# DDR4_Conn.net
KiCad netlist of a schematic drawn in Altium Designer
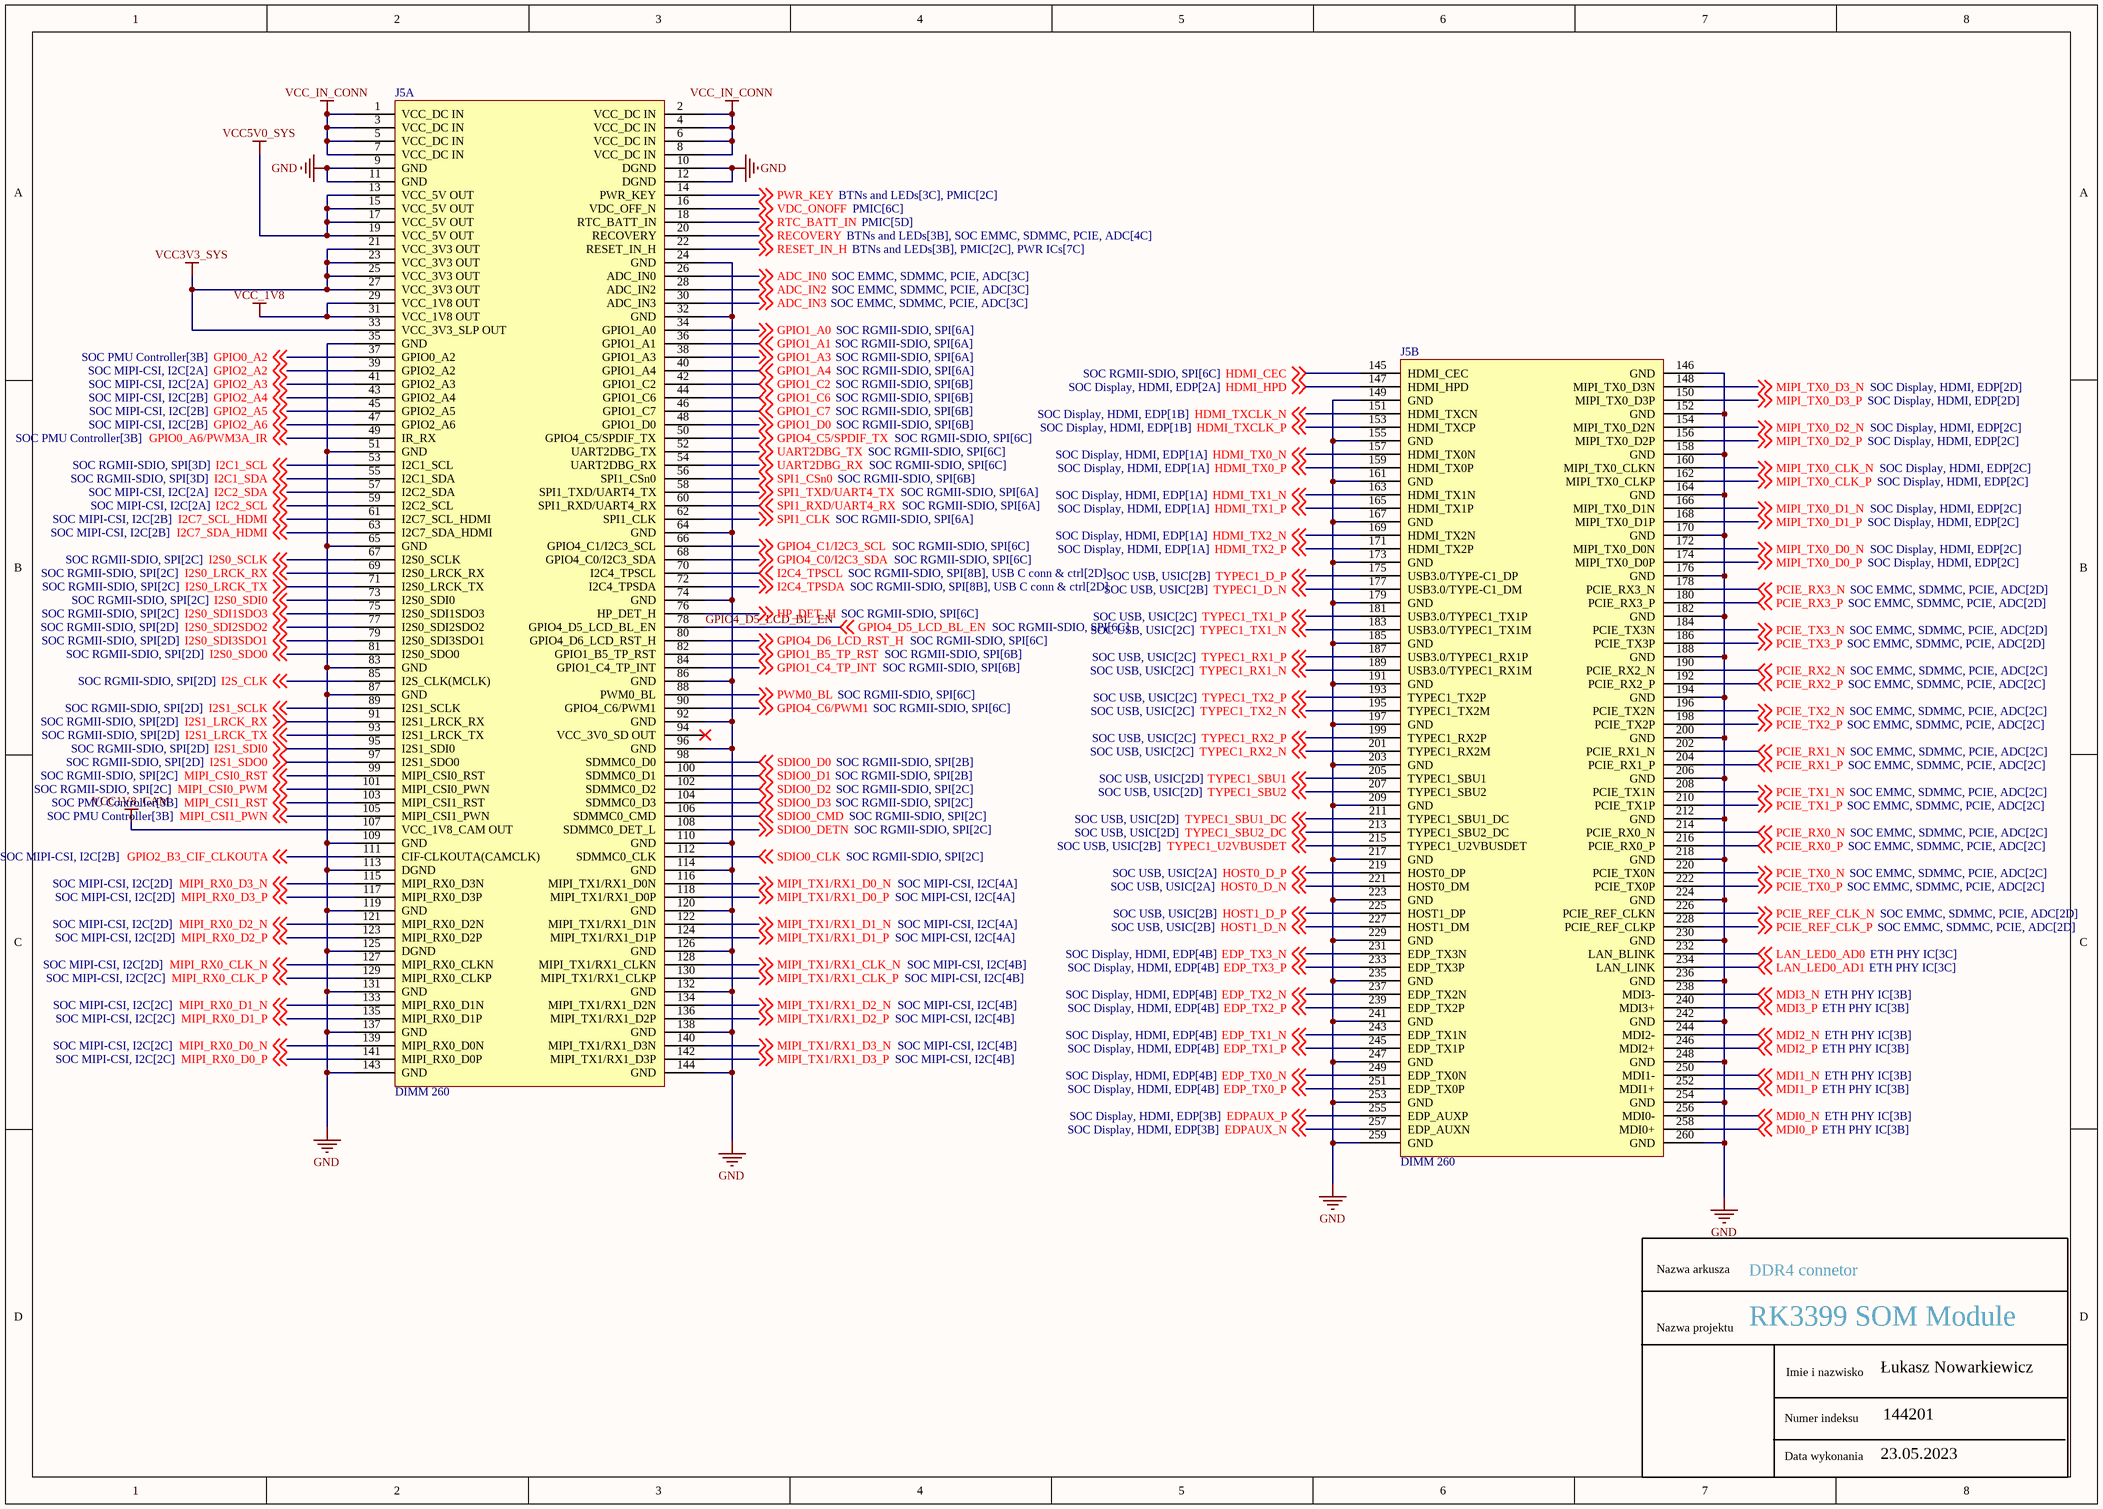
[diagram p0: DDR4 Conn.SchDoc]

(export (version "E")
  (design (tool "Eeschema 10.0.6"))
  (components
    (comp (ref "J5")
      (value "DIMM 260")
      (footprint "DIMM260_DDR4")
      (description "Dimm 260 pin smd plating on pcb")
      (fields (field (name "MANUFACTURER") "NA"))
      (libsource (lib "RK3399 _Module_Schlib") (part "CON-DIMM_260-SMD"))
    )
  )
  (nets
    (net (code "1") (name "ADC_IN0") (class "Default")
      (node (ref "J5") (pin "26") (pinfunction "ADC_IN0_26") (pintype "passive"))
    )
    (net (code "2") (name "ADC_IN2") (class "Default")
      (node (ref "J5") (pin "28") (pinfunction "ADC_IN2_28") (pintype "passive"))
    )
    (net (code "3") (name "ADC_IN3") (class "Default")
      (node (ref "J5") (pin "30") (pinfunction "ADC_IN3_30") (pintype "passive"))
    )
    (net (code "4") (name "EDPAUX_N") (class "Default")
      (node (ref "J5") (pin "257") (pinfunction "EDP_AUXN_257") (pintype "passive"))
    )
    (net (code "5") (name "EDPAUX_P") (class "Default")
      (node (ref "J5") (pin "255") (pinfunction "EDP_AUXP_255") (pintype "passive"))
    )
    (net (code "6") (name "EDP_TX0_N") (class "Default")
      (node (ref "J5") (pin "249") (pinfunction "EDP_TX0N_249") (pintype "passive"))
    )
    (net (code "7") (name "EDP_TX0_P") (class "Default")
      (node (ref "J5") (pin "251") (pinfunction "EDP_TX0P_251") (pintype "passive"))
    )
    (net (code "8") (name "EDP_TX1_N") (class "Default")
      (node (ref "J5") (pin "243") (pinfunction "EDP_TX1N_243") (pintype "passive"))
    )
    (net (code "9") (name "EDP_TX1_P") (class "Default")
      (node (ref "J5") (pin "245") (pinfunction "EDP_TX1P_245") (pintype "passive"))
    )
    (net (code "10") (name "EDP_TX2_N") (class "Default")
      (node (ref "J5") (pin "237") (pinfunction "EDP_TX2N_237") (pintype "passive"))
    )
    (net (code "11") (name "EDP_TX2_P") (class "Default")
      (node (ref "J5") (pin "239") (pinfunction "EDP_TX2P_239") (pintype "passive"))
    )
    (net (code "12") (name "EDP_TX3_N") (class "Default")
      (node (ref "J5") (pin "231") (pinfunction "EDP_TX3N_231") (pintype "passive"))
    )
    (net (code "13") (name "EDP_TX3_P") (class "Default")
      (node (ref "J5") (pin "233") (pinfunction "EDP_TX3P_233") (pintype "passive"))
    )
    (net (code "14") (name "GND") (class "Default")
      (node (ref "J5") (pin "10") (pinfunction "DGND_10") (pintype "passive"))
      (node (ref "J5") (pin "109") (pinfunction "GND_109") (pintype "passive"))
      (node (ref "J5") (pin "11") (pinfunction "GND_11") (pintype "passive"))
      (node (ref "J5") (pin "110") (pinfunction "GND_110") (pintype "passive"))
      (node (ref "J5") (pin "113") (pinfunction "DGND_113") (pintype "passive"))
      (node (ref "J5") (pin "114") (pinfunction "GND_114") (pintype "passive"))
      (node (ref "J5") (pin "119") (pinfunction "GND_119") (pintype "passive"))
      (node (ref "J5") (pin "12") (pinfunction "DGND_12") (pintype "passive"))
      (node (ref "J5") (pin "120") (pinfunction "GND_120") (pintype "passive"))
      (node (ref "J5") (pin "125") (pinfunction "DGND_125") (pintype "passive"))
      (node (ref "J5") (pin "126") (pinfunction "GND_126") (pintype "passive"))
      (node (ref "J5") (pin "131") (pinfunction "GND_131") (pintype "passive"))
      (node (ref "J5") (pin "132") (pinfunction "GND_132") (pintype "passive"))
      (node (ref "J5") (pin "137") (pinfunction "GND_137") (pintype "passive"))
      (node (ref "J5") (pin "138") (pinfunction "GND_138") (pintype "passive"))
      (node (ref "J5") (pin "143") (pinfunction "GND_143") (pintype "passive"))
      (node (ref "J5") (pin "144") (pinfunction "GND_144") (pintype "passive"))
      (node (ref "J5") (pin "146") (pinfunction "GND_146") (pintype "passive"))
      (node (ref "J5") (pin "149") (pinfunction "GND_149") (pintype "passive"))
      (node (ref "J5") (pin "152") (pinfunction "GND_152") (pintype "passive"))
      (node (ref "J5") (pin "155") (pinfunction "GND_155") (pintype "passive"))
      (node (ref "J5") (pin "158") (pinfunction "GND_158") (pintype "passive"))
      (node (ref "J5") (pin "161") (pinfunction "GND_161") (pintype "passive"))
      (node (ref "J5") (pin "164") (pinfunction "GND_164") (pintype "passive"))
      (node (ref "J5") (pin "167") (pinfunction "GND_167") (pintype "passive"))
      (node (ref "J5") (pin "170") (pinfunction "GND_170") (pintype "passive"))
      (node (ref "J5") (pin "173") (pinfunction "GND_173") (pintype "passive"))
      (node (ref "J5") (pin "176") (pinfunction "GND_176") (pintype "passive"))
      (node (ref "J5") (pin "179") (pinfunction "GND_179") (pintype "passive"))
      (node (ref "J5") (pin "182") (pinfunction "GND_182") (pintype "passive"))
      (node (ref "J5") (pin "185") (pinfunction "GND_185") (pintype "passive"))
      (node (ref "J5") (pin "188") (pinfunction "GND_188") (pintype "passive"))
      (node (ref "J5") (pin "191") (pinfunction "GND_191") (pintype "passive"))
      (node (ref "J5") (pin "194") (pinfunction "GND_194") (pintype "passive"))
      (node (ref "J5") (pin "197") (pinfunction "GND_197") (pintype "passive"))
      (node (ref "J5") (pin "200") (pinfunction "GND_200") (pintype "passive"))
      (node (ref "J5") (pin "203") (pinfunction "GND_203") (pintype "passive"))
      (node (ref "J5") (pin "206") (pinfunction "GND_206") (pintype "passive"))
      (node (ref "J5") (pin "209") (pinfunction "GND_209") (pintype "passive"))
      (node (ref "J5") (pin "212") (pinfunction "GND_212") (pintype "passive"))
      (node (ref "J5") (pin "217") (pinfunction "GND_217") (pintype "passive"))
      (node (ref "J5") (pin "218") (pinfunction "GND_218") (pintype "passive"))
      (node (ref "J5") (pin "223") (pinfunction "GND_223") (pintype "passive"))
      (node (ref "J5") (pin "224") (pinfunction "GND_224") (pintype "passive"))
      (node (ref "J5") (pin "229") (pinfunction "GND_229") (pintype "passive"))
      (node (ref "J5") (pin "230") (pinfunction "GND_230") (pintype "passive"))
      (node (ref "J5") (pin "235") (pinfunction "GND_235") (pintype "passive"))
      (node (ref "J5") (pin "236") (pinfunction "GND_236") (pintype "passive"))
      (node (ref "J5") (pin "24") (pinfunction "GND_24") (pintype "passive"))
      (node (ref "J5") (pin "241") (pinfunction "GND_241") (pintype "passive"))
      (node (ref "J5") (pin "242") (pinfunction "GND_242") (pintype "passive"))
      (node (ref "J5") (pin "247") (pinfunction "GND_247") (pintype "passive"))
      (node (ref "J5") (pin "248") (pinfunction "GND_248") (pintype "passive"))
      (node (ref "J5") (pin "253") (pinfunction "GND_253") (pintype "passive"))
      (node (ref "J5") (pin "254") (pinfunction "GND_254") (pintype "passive"))
      (node (ref "J5") (pin "259") (pinfunction "GND_259") (pintype "passive"))
      (node (ref "J5") (pin "260") (pinfunction "GND_260") (pintype "passive"))
      (node (ref "J5") (pin "32") (pinfunction "GND_32") (pintype "passive"))
      (node (ref "J5") (pin "35") (pinfunction "GND_35") (pintype "passive"))
      (node (ref "J5") (pin "51") (pinfunction "GND_51") (pintype "passive"))
      (node (ref "J5") (pin "64") (pinfunction "GND_64") (pintype "passive"))
      (node (ref "J5") (pin "65") (pinfunction "GND_65") (pintype "passive"))
      (node (ref "J5") (pin "74") (pinfunction "GND_74") (pintype "passive"))
      (node (ref "J5") (pin "83") (pinfunction "GND_83") (pintype "passive"))
      (node (ref "J5") (pin "86") (pinfunction "GND_86") (pintype "passive"))
      (node (ref "J5") (pin "87") (pinfunction "GND_87") (pintype "passive"))
      (node (ref "J5") (pin "9") (pinfunction "GND_9") (pintype "passive"))
      (node (ref "J5") (pin "92") (pinfunction "GND_92") (pintype "passive"))
      (node (ref "J5") (pin "96") (pinfunction "GND_96") (pintype "passive"))
    )
    (net (code "15") (name "GPIO0_A2") (class "Default")
      (node (ref "J5") (pin "37") (pinfunction "GPIO0_A2_37") (pintype "passive"))
    )
    (net (code "16") (name "GPIO0_A6{slash}PWM3A_IR") (class "Default")
      (node (ref "J5") (pin "49") (pinfunction "IR_RX_49") (pintype "passive"))
    )
    (net (code "17") (name "GPIO1_A0") (class "Default")
      (node (ref "J5") (pin "34") (pinfunction "GPIO1_A0_34") (pintype "passive"))
    )
    (net (code "18") (name "GPIO1_A1") (class "Default")
      (node (ref "J5") (pin "36") (pinfunction "GPIO1_A1_36") (pintype "passive"))
    )
    (net (code "19") (name "GPIO1_A3") (class "Default")
      (node (ref "J5") (pin "38") (pinfunction "GPIO1_A3_38") (pintype "passive"))
    )
    (net (code "20") (name "GPIO1_A4") (class "Default")
      (node (ref "J5") (pin "40") (pinfunction "GPIO1_A4_40") (pintype "passive"))
    )
    (net (code "21") (name "GPIO1_B5_TP_RST") (class "Default")
      (node (ref "J5") (pin "82") (pinfunction "GPIO1_B5_TP_RST_82") (pintype "passive"))
    )
    (net (code "22") (name "GPIO1_C2") (class "Default")
      (node (ref "J5") (pin "42") (pinfunction "GPIO1_C2_42") (pintype "passive"))
    )
    (net (code "23") (name "GPIO1_C4_TP_INT") (class "Default")
      (node (ref "J5") (pin "84") (pinfunction "GPIO1_C4_TP_INT_84") (pintype "passive"))
    )
    (net (code "24") (name "GPIO1_C6") (class "Default")
      (node (ref "J5") (pin "44") (pinfunction "GPIO1_C6_44") (pintype "passive"))
    )
    (net (code "25") (name "GPIO1_C7") (class "Default")
      (node (ref "J5") (pin "46") (pinfunction "GPIO1_C7_46") (pintype "passive"))
    )
    (net (code "26") (name "GPIO1_D0") (class "Default")
      (node (ref "J5") (pin "48") (pinfunction "GPIO1_D0_48") (pintype "passive"))
    )
    (net (code "27") (name "GPIO2_A2") (class "Default")
      (node (ref "J5") (pin "39") (pinfunction "GPIO2_A2_39") (pintype "passive"))
    )
    (net (code "28") (name "GPIO2_A3") (class "Default")
      (node (ref "J5") (pin "41") (pinfunction "GPIO2_A3_41") (pintype "passive"))
    )
    (net (code "29") (name "GPIO2_A4") (class "Default")
      (node (ref "J5") (pin "43") (pinfunction "GPIO2_A4_43") (pintype "passive"))
    )
    (net (code "30") (name "GPIO2_A5") (class "Default")
      (node (ref "J5") (pin "45") (pinfunction "GPIO2_A5_45") (pintype "passive"))
    )
    (net (code "31") (name "GPIO2_A6") (class "Default")
      (node (ref "J5") (pin "47") (pinfunction "GPIO2_A6_47") (pintype "passive"))
    )
    (net (code "32") (name "GPIO2_B3_CIF_CLKOUTA") (class "Default")
      (node (ref "J5") (pin "111") (pinfunction "CIF-CLKOUTA(CAMCLK)_111") (pintype "passive"))
    )
    (net (code "33") (name "GPIO4_C0{slash}I2C3_SDA") (class "Default")
      (node (ref "J5") (pin "68") (pinfunction "GPIO4_C0/I2C3_SDA_68") (pintype "passive"))
    )
    (net (code "34") (name "GPIO4_C1{slash}I2C3_SCL") (class "Default")
      (node (ref "J5") (pin "66") (pinfunction "GPIO4_C1/I2C3_SCL_66") (pintype "passive"))
    )
    (net (code "35") (name "GPIO4_C5{slash}SPDIF_TX") (class "Default")
      (node (ref "J5") (pin "50") (pinfunction "GPIO4_C5/SPDIF_TX_50") (pintype "passive"))
    )
    (net (code "36") (name "GPIO4_C6{slash}PWM1") (class "Default")
      (node (ref "J5") (pin "90") (pinfunction "GPIO4_C6/PWM1_90") (pintype "passive"))
    )
    (net (code "37") (name "GPIO4_D5_LCD_BL_EN") (class "Default")
      (node (ref "J5") (pin "78") (pinfunction "GPIO4_D5_LCD_BL_EN_78") (pintype "passive"))
    )
    (net (code "38") (name "GPIO4_D6_LCD_RST_H") (class "Default")
      (node (ref "J5") (pin "80") (pinfunction "GPIO4_D6_LCD_RST_H_80") (pintype "passive"))
    )
    (net (code "39") (name "HDMI_CEC") (class "Default")
      (node (ref "J5") (pin "145") (pinfunction "HDMI_CEC_145") (pintype "passive"))
    )
    (net (code "40") (name "HDMI_HPD") (class "Default")
      (node (ref "J5") (pin "147") (pinfunction "HDMI_HPD_147") (pintype "passive"))
    )
    (net (code "41") (name "HDMI_TX0_N") (class "Default")
      (node (ref "J5") (pin "157") (pinfunction "HDMI_TX0N_157") (pintype "passive"))
    )
    (net (code "42") (name "HDMI_TX0_P") (class "Default")
      (node (ref "J5") (pin "159") (pinfunction "HDMI_TX0P_159") (pintype "passive"))
    )
    (net (code "43") (name "HDMI_TX1_N") (class "Default")
      (node (ref "J5") (pin "163") (pinfunction "HDMI_TX1N_163") (pintype "passive"))
    )
    (net (code "44") (name "HDMI_TX1_P") (class "Default")
      (node (ref "J5") (pin "165") (pinfunction "HDMI_TX1P_165") (pintype "passive"))
    )
    (net (code "45") (name "HDMI_TX2_N") (class "Default")
      (node (ref "J5") (pin "169") (pinfunction "HDMI_TX2N_169") (pintype "passive"))
    )
    (net (code "46") (name "HDMI_TX2_P") (class "Default")
      (node (ref "J5") (pin "171") (pinfunction "HDMI_TX2P_171") (pintype "passive"))
    )
    (net (code "47") (name "HDMI_TXCLK_N") (class "Default")
      (node (ref "J5") (pin "151") (pinfunction "HDMI_TXCN_151") (pintype "passive"))
    )
    (net (code "48") (name "HDMI_TXCLK_P") (class "Default")
      (node (ref "J5") (pin "153") (pinfunction "HDMI_TXCP_153") (pintype "passive"))
    )
    (net (code "49") (name "HOST0_D_N") (class "Default")
      (node (ref "J5") (pin "221") (pinfunction "HOST0_DM_221") (pintype "passive"))
    )
    (net (code "50") (name "HOST0_D_P") (class "Default")
      (node (ref "J5") (pin "219") (pinfunction "HOST0_DP_219") (pintype "passive"))
    )
    (net (code "51") (name "HOST1_D_N") (class "Default")
      (node (ref "J5") (pin "227") (pinfunction "HOST1_DM_227") (pintype "passive"))
    )
    (net (code "52") (name "HOST1_D_P") (class "Default")
      (node (ref "J5") (pin "225") (pinfunction "HOST1_DP_225") (pintype "passive"))
    )
    (net (code "53") (name "HP_DET_H") (class "Default")
      (node (ref "J5") (pin "76") (pinfunction "HP_DET_H_76") (pintype "passive"))
    )
    (net (code "54") (name "I2C1_SCL") (class "Default")
      (node (ref "J5") (pin "53") (pinfunction "I2C1_SCL_53") (pintype "passive"))
    )
    (net (code "55") (name "I2C1_SDA") (class "Default")
      (node (ref "J5") (pin "55") (pinfunction "I2C1_SDA_55") (pintype "passive"))
    )
    (net (code "56") (name "I2C2_SCL") (class "Default")
      (node (ref "J5") (pin "59") (pinfunction "I2C2_SCL_59") (pintype "passive"))
    )
    (net (code "57") (name "I2C2_SDA") (class "Default")
      (node (ref "J5") (pin "57") (pinfunction "I2C2_SDA_57") (pintype "passive"))
    )
    (net (code "58") (name "I2C4_TPSCL") (class "Default")
      (node (ref "J5") (pin "70") (pinfunction "I2C4_TPSCL_70") (pintype "passive"))
    )
    (net (code "59") (name "I2C4_TPSDA") (class "Default")
      (node (ref "J5") (pin "72") (pinfunction "I2C4_TPSDA_72") (pintype "passive"))
    )
    (net (code "60") (name "I2C7_SCL_HDMI") (class "Default")
      (node (ref "J5") (pin "61") (pinfunction "I2C7_SCL_HDMI_61") (pintype "passive"))
    )
    (net (code "61") (name "I2C7_SDA_HDMI") (class "Default")
      (node (ref "J5") (pin "63") (pinfunction "I2C7_SDA_HDMI_63") (pintype "passive"))
    )
    (net (code "62") (name "I2S0_LRCK_RX") (class "Default")
      (node (ref "J5") (pin "69") (pinfunction "I2S0_LRCK_RX_69") (pintype "passive"))
    )
    (net (code "63") (name "I2S0_LRCK_TX") (class "Default")
      (node (ref "J5") (pin "71") (pinfunction "I2S0_LRCK_TX_71") (pintype "passive"))
    )
    (net (code "64") (name "I2S0_SCLK") (class "Default")
      (node (ref "J5") (pin "67") (pinfunction "I2S0_SCLK_67") (pintype "passive"))
    )
    (net (code "65") (name "I2S0_SDI0") (class "Default")
      (node (ref "J5") (pin "73") (pinfunction "I2S0_SDI0_73") (pintype "passive"))
    )
    (net (code "66") (name "I2S0_SDI1SDO3") (class "Default")
      (node (ref "J5") (pin "75") (pinfunction "I2S0_SDI1SDO3_75") (pintype "passive"))
    )
    (net (code "67") (name "I2S0_SDI2SDO2") (class "Default")
      (node (ref "J5") (pin "77") (pinfunction "I2S0_SDI2SDO2_77") (pintype "passive"))
    )
    (net (code "68") (name "I2S0_SDI3SDO1") (class "Default")
      (node (ref "J5") (pin "79") (pinfunction "I2S0_SDI3SDO1_79") (pintype "passive"))
    )
    (net (code "69") (name "I2S0_SDO0") (class "Default")
      (node (ref "J5") (pin "81") (pinfunction "I2S0_SDO0_81") (pintype "passive"))
    )
    (net (code "70") (name "I2S1_LRCK_RX") (class "Default")
      (node (ref "J5") (pin "91") (pinfunction "I2S1_LRCK_RX_91") (pintype "passive"))
    )
    (net (code "71") (name "I2S1_LRCK_TX") (class "Default")
      (node (ref "J5") (pin "93") (pinfunction "I2S1_LRCK_TX_93") (pintype "passive"))
    )
    (net (code "72") (name "I2S1_SCLK") (class "Default")
      (node (ref "J5") (pin "89") (pinfunction "I2S1_SCLK_89") (pintype "passive"))
    )
    (net (code "73") (name "I2S1_SDI0") (class "Default")
      (node (ref "J5") (pin "95") (pinfunction "I2S1_SDI0_95") (pintype "passive"))
    )
    (net (code "74") (name "I2S1_SDO0") (class "Default")
      (node (ref "J5") (pin "97") (pinfunction "I2S1_SDO0_97") (pintype "passive"))
    )
    (net (code "75") (name "I2S_CLK") (class "Default")
      (node (ref "J5") (pin "85") (pinfunction "I2S_CLK(MCLK)_85") (pintype "passive"))
    )
    (net (code "76") (name "LAN_LED0_AD0") (class "Default")
      (node (ref "J5") (pin "232") (pinfunction "LAN_BLINK_232") (pintype "passive"))
    )
    (net (code "77") (name "LAN_LED0_AD1") (class "Default")
      (node (ref "J5") (pin "234") (pinfunction "LAN_LINK_234") (pintype "passive"))
    )
    (net (code "78") (name "MDI0_N") (class "Default")
      (node (ref "J5") (pin "256") (pinfunction "MDI0-_256") (pintype "passive"))
    )
    (net (code "79") (name "MDI0_P") (class "Default")
      (node (ref "J5") (pin "258") (pinfunction "MDI0+_258") (pintype "passive"))
    )
    (net (code "80") (name "MDI1_N") (class "Default")
      (node (ref "J5") (pin "250") (pinfunction "MDI1-_250") (pintype "passive"))
    )
    (net (code "81") (name "MDI1_P") (class "Default")
      (node (ref "J5") (pin "252") (pinfunction "MDI1+_252") (pintype "passive"))
    )
    (net (code "82") (name "MDI2_N") (class "Default")
      (node (ref "J5") (pin "244") (pinfunction "MDI2-_244") (pintype "passive"))
    )
    (net (code "83") (name "MDI2_P") (class "Default")
      (node (ref "J5") (pin "246") (pinfunction "MDI2+_246") (pintype "passive"))
    )
    (net (code "84") (name "MDI3_N") (class "Default")
      (node (ref "J5") (pin "238") (pinfunction "MDI3-_238") (pintype "passive"))
    )
    (net (code "85") (name "MDI3_P") (class "Default")
      (node (ref "J5") (pin "240") (pinfunction "MDI3+_240") (pintype "passive"))
    )
    (net (code "86") (name "MIPI_CSI0_PWM") (class "Default")
      (node (ref "J5") (pin "101") (pinfunction "MIPI_CSI0_PWN_101") (pintype "passive"))
    )
    (net (code "87") (name "MIPI_CSI0_RST") (class "Default")
      (node (ref "J5") (pin "99") (pinfunction "MIPI_CSI0_RST_99") (pintype "passive"))
    )
    (net (code "88") (name "MIPI_CSI1_PWN") (class "Default")
      (node (ref "J5") (pin "105") (pinfunction "MIPI_CSI1_PWN_105") (pintype "passive"))
    )
    (net (code "89") (name "MIPI_CSI1_RST") (class "Default")
      (node (ref "J5") (pin "103") (pinfunction "MIPI_CSI1_RST_103") (pintype "passive"))
    )
    (net (code "90") (name "MIPI_RX0_CLK_N") (class "Default")
      (node (ref "J5") (pin "127") (pinfunction "MIPI_RX0_CLKN_127") (pintype "passive"))
    )
    (net (code "91") (name "MIPI_RX0_CLK_P") (class "Default")
      (node (ref "J5") (pin "129") (pinfunction "MIPI_RX0_CLKP_129") (pintype "passive"))
    )
    (net (code "92") (name "MIPI_RX0_D0_N") (class "Default")
      (node (ref "J5") (pin "139") (pinfunction "MIPI_RX0_D0N_139") (pintype "passive"))
    )
    (net (code "93") (name "MIPI_RX0_D0_P") (class "Default")
      (node (ref "J5") (pin "141") (pinfunction "MIPI_RX0_D0P_141") (pintype "passive"))
    )
    (net (code "94") (name "MIPI_RX0_D1_N") (class "Default")
      (node (ref "J5") (pin "133") (pinfunction "MIPI_RX0_D1N_133") (pintype "passive"))
    )
    (net (code "95") (name "MIPI_RX0_D1_P") (class "Default")
      (node (ref "J5") (pin "135") (pinfunction "MIPI_RX0_D1P_135") (pintype "passive"))
    )
    (net (code "96") (name "MIPI_RX0_D2_N") (class "Default")
      (node (ref "J5") (pin "121") (pinfunction "MIPI_RX0_D2N_121") (pintype "passive"))
    )
    (net (code "97") (name "MIPI_RX0_D2_P") (class "Default")
      (node (ref "J5") (pin "123") (pinfunction "MIPI_RX0_D2P_123") (pintype "passive"))
    )
    (net (code "98") (name "MIPI_RX0_D3_N") (class "Default")
      (node (ref "J5") (pin "115") (pinfunction "MIPI_RX0_D3N_115") (pintype "passive"))
    )
    (net (code "99") (name "MIPI_RX0_D3_P") (class "Default")
      (node (ref "J5") (pin "117") (pinfunction "MIPI_RX0_D3P_117") (pintype "passive"))
    )
    (net (code "100") (name "MIPI_TX0_CLK_N") (class "Default")
      (node (ref "J5") (pin "160") (pinfunction "MIPI_TX0_CLKN_160") (pintype "passive"))
    )
    (net (code "101") (name "MIPI_TX0_CLK_P") (class "Default")
      (node (ref "J5") (pin "162") (pinfunction "MIPI_TX0_CLKP_162") (pintype "passive"))
    )
    (net (code "102") (name "MIPI_TX0_D0_N") (class "Default")
      (node (ref "J5") (pin "172") (pinfunction "MIPI_TX0_D0N_172") (pintype "passive"))
    )
    (net (code "103") (name "MIPI_TX0_D0_P") (class "Default")
      (node (ref "J5") (pin "174") (pinfunction "MIPI_TX0_D0P_174") (pintype "passive"))
    )
    (net (code "104") (name "MIPI_TX0_D1_N") (class "Default")
      (node (ref "J5") (pin "166") (pinfunction "MIPI_TX0_D1N_166") (pintype "passive"))
    )
    (net (code "105") (name "MIPI_TX0_D1_P") (class "Default")
      (node (ref "J5") (pin "168") (pinfunction "MIPI_TX0_D1P_168") (pintype "passive"))
    )
    (net (code "106") (name "MIPI_TX0_D2_N") (class "Default")
      (node (ref "J5") (pin "154") (pinfunction "MIPI_TX0_D2N_154") (pintype "passive"))
    )
    (net (code "107") (name "MIPI_TX0_D2_P") (class "Default")
      (node (ref "J5") (pin "156") (pinfunction "MIPI_TX0_D2P_156") (pintype "passive"))
    )
    (net (code "108") (name "MIPI_TX0_D3_N") (class "Default")
      (node (ref "J5") (pin "148") (pinfunction "MIPI_TX0_D3N_148") (pintype "passive"))
    )
    (net (code "109") (name "MIPI_TX0_D3_P") (class "Default")
      (node (ref "J5") (pin "150") (pinfunction "MIPI_TX0_D3P_150") (pintype "passive"))
    )
    (net (code "110") (name "MIPI_TX1{slash}RX1_CLK_N") (class "Default")
      (node (ref "J5") (pin "128") (pinfunction "MIPI_TX1/RX1_CLKN_128") (pintype "passive"))
    )
    (net (code "111") (name "MIPI_TX1{slash}RX1_CLK_P") (class "Default")
      (node (ref "J5") (pin "130") (pinfunction "MIPI_TX1/RX1_CLKP_130") (pintype "passive"))
    )
    (net (code "112") (name "MIPI_TX1{slash}RX1_D0_N") (class "Default")
      (node (ref "J5") (pin "116") (pinfunction "MIPI_TX1/RX1_D0N_116") (pintype "passive"))
    )
    (net (code "113") (name "MIPI_TX1{slash}RX1_D0_P") (class "Default")
      (node (ref "J5") (pin "118") (pinfunction "MIPI_TX1/RX1_D0P_118") (pintype "passive"))
    )
    (net (code "114") (name "MIPI_TX1{slash}RX1_D1_N") (class "Default")
      (node (ref "J5") (pin "122") (pinfunction "MIPI_TX1/RX1_D1N_122") (pintype "passive"))
    )
    (net (code "115") (name "MIPI_TX1{slash}RX1_D1_P") (class "Default")
      (node (ref "J5") (pin "124") (pinfunction "MIPI_TX1/RX1_D1P_124") (pintype "passive"))
    )
    (net (code "116") (name "MIPI_TX1{slash}RX1_D2_N") (class "Default")
      (node (ref "J5") (pin "134") (pinfunction "MIPI_TX1/RX1_D2N_134") (pintype "passive"))
    )
    (net (code "117") (name "MIPI_TX1{slash}RX1_D2_P") (class "Default")
      (node (ref "J5") (pin "136") (pinfunction "MIPI_TX1/RX1_D2P_136") (pintype "passive"))
    )
    (net (code "118") (name "MIPI_TX1{slash}RX1_D3_N") (class "Default")
      (node (ref "J5") (pin "140") (pinfunction "MIPI_TX1/RX1_D3N_140") (pintype "passive"))
    )
    (net (code "119") (name "MIPI_TX1{slash}RX1_D3_P") (class "Default")
      (node (ref "J5") (pin "142") (pinfunction "MIPI_TX1/RX1_D3P_142") (pintype "passive"))
    )
    (net (code "120") (name "PCIE_REF_CLK_N") (class "Default")
      (node (ref "J5") (pin "226") (pinfunction "PCIE_REF_CLKN_226") (pintype "passive"))
    )
    (net (code "121") (name "PCIE_REF_CLK_P") (class "Default")
      (node (ref "J5") (pin "228") (pinfunction "PCIE_REF_CLKP_228") (pintype "passive"))
    )
    (net (code "122") (name "PCIE_RX0_N") (class "Default")
      (node (ref "J5") (pin "214") (pinfunction "PCIE_RX0_N_214") (pintype "passive"))
    )
    (net (code "123") (name "PCIE_RX0_P") (class "Default")
      (node (ref "J5") (pin "216") (pinfunction "PCIE_RX0_P_216") (pintype "passive"))
    )
    (net (code "124") (name "PCIE_RX1_N") (class "Default")
      (node (ref "J5") (pin "202") (pinfunction "PCIE_RX1_N_202") (pintype "passive"))
    )
    (net (code "125") (name "PCIE_RX1_P") (class "Default")
      (node (ref "J5") (pin "204") (pinfunction "PCIE_RX1_P_204") (pintype "passive"))
    )
    (net (code "126") (name "PCIE_RX2_N") (class "Default")
      (node (ref "J5") (pin "190") (pinfunction "PCIE_RX2_N_190") (pintype "passive"))
    )
    (net (code "127") (name "PCIE_RX2_P") (class "Default")
      (node (ref "J5") (pin "192") (pinfunction "PCIE_RX2_P_192") (pintype "passive"))
    )
    (net (code "128") (name "PCIE_RX3_N") (class "Default")
      (node (ref "J5") (pin "178") (pinfunction "PCIE_RX3_N_178") (pintype "passive"))
    )
    (net (code "129") (name "PCIE_RX3_P") (class "Default")
      (node (ref "J5") (pin "180") (pinfunction "PCIE_RX3_P_180") (pintype "passive"))
    )
    (net (code "130") (name "PCIE_TX0_N") (class "Default")
      (node (ref "J5") (pin "220") (pinfunction "PCIE_TX0N_220") (pintype "passive"))
    )
    (net (code "131") (name "PCIE_TX0_P") (class "Default")
      (node (ref "J5") (pin "222") (pinfunction "PCIE_TX0P_222") (pintype "passive"))
    )
    (net (code "132") (name "PCIE_TX1_N") (class "Default")
      (node (ref "J5") (pin "208") (pinfunction "PCIE_TX1N_208") (pintype "passive"))
    )
    (net (code "133") (name "PCIE_TX1_P") (class "Default")
      (node (ref "J5") (pin "210") (pinfunction "PCIE_TX1P_210") (pintype "passive"))
    )
    (net (code "134") (name "PCIE_TX2_N") (class "Default")
      (node (ref "J5") (pin "196") (pinfunction "PCIE_TX2N_196") (pintype "passive"))
    )
    (net (code "135") (name "PCIE_TX2_P") (class "Default")
      (node (ref "J5") (pin "198") (pinfunction "PCIE_TX2P_198") (pintype "passive"))
    )
    (net (code "136") (name "PCIE_TX3_N") (class "Default")
      (node (ref "J5") (pin "184") (pinfunction "PCIE_TX3N_184") (pintype "passive"))
    )
    (net (code "137") (name "PCIE_TX3_P") (class "Default")
      (node (ref "J5") (pin "186") (pinfunction "PCIE_TX3P_186") (pintype "passive"))
    )
    (net (code "138") (name "PWM0_BL") (class "Default")
      (node (ref "J5") (pin "88") (pinfunction "PWM0_BL_88") (pintype "passive"))
    )
    (net (code "139") (name "PWR_KEY") (class "Default")
      (node (ref "J5") (pin "14") (pinfunction "PWR_KEY_14") (pintype "passive"))
    )
    (net (code "140") (name "RECOVERY") (class "Default")
      (node (ref "J5") (pin "20") (pinfunction "RECOVERY_20") (pintype "passive"))
    )
    (net (code "141") (name "RESET_IN_H") (class "Default")
      (node (ref "J5") (pin "22") (pinfunction "RESET_IN_H_22") (pintype "passive"))
    )
    (net (code "142") (name "RTC_BATT_IN") (class "Default")
      (node (ref "J5") (pin "18") (pinfunction "RTC_BATT_IN_18") (pintype "passive"))
    )
    (net (code "143") (name "SDIO0_CLK") (class "Default")
      (node (ref "J5") (pin "112") (pinfunction "SDMMC0_CLK_112") (pintype "passive"))
    )
    (net (code "144") (name "SDIO0_CMD") (class "Default")
      (node (ref "J5") (pin "106") (pinfunction "SDMMC0_CMD_106") (pintype "passive"))
    )
    (net (code "145") (name "SDIO0_D0") (class "Default")
      (node (ref "J5") (pin "98") (pinfunction "SDMMC0_D0_98") (pintype "passive"))
    )
    (net (code "146") (name "SDIO0_D1") (class "Default")
      (node (ref "J5") (pin "100") (pinfunction "SDMMC0_D1_100") (pintype "passive"))
    )
    (net (code "147") (name "SDIO0_D2") (class "Default")
      (node (ref "J5") (pin "102") (pinfunction "SDMMC0_D2_102") (pintype "passive"))
    )
    (net (code "148") (name "SDIO0_D3") (class "Default")
      (node (ref "J5") (pin "104") (pinfunction "SDMMC0_D3_104") (pintype "passive"))
    )
    (net (code "149") (name "SDIO0_DETN") (class "Default")
      (node (ref "J5") (pin "108") (pinfunction "SDMMC0_DET_L_108") (pintype "passive"))
    )
    (net (code "150") (name "SPI1_CLK") (class "Default")
      (node (ref "J5") (pin "62") (pinfunction "SPI1_CLK_62") (pintype "passive"))
    )
    (net (code "151") (name "SPI1_CSn0") (class "Default")
      (node (ref "J5") (pin "56") (pinfunction "SPI1_CSn0_56") (pintype "passive"))
    )
    (net (code "152") (name "SPI1_RXD{slash}UART4_RX") (class "Default")
      (node (ref "J5") (pin "60") (pinfunction "SPI1_RXD/UART4_RX_60") (pintype "passive"))
    )
    (net (code "153") (name "SPI1_TXD{slash}UART4_TX") (class "Default")
      (node (ref "J5") (pin "58") (pinfunction "SPI1_TXD/UART4_TX_58") (pintype "passive"))
    )
    (net (code "154") (name "TYPEC1_D_N") (class "Default")
      (node (ref "J5") (pin "177") (pinfunction "USB3.0/TYPE-C1_DM_177") (pintype "passive"))
    )
    (net (code "155") (name "TYPEC1_D_P") (class "Default")
      (node (ref "J5") (pin "175") (pinfunction "USB3.0/TYPE-C1_DP_175") (pintype "passive"))
    )
    (net (code "156") (name "TYPEC1_RX1_N") (class "Default")
      (node (ref "J5") (pin "189") (pinfunction "USB3.0/TYPEC1_RX1M_189") (pintype "passive"))
    )
    (net (code "157") (name "TYPEC1_RX1_P") (class "Default")
      (node (ref "J5") (pin "187") (pinfunction "USB3.0/TYPEC1_RX1P_187") (pintype "passive"))
    )
    (net (code "158") (name "TYPEC1_RX2_N") (class "Default")
      (node (ref "J5") (pin "201") (pinfunction "TYPEC1_RX2M_201") (pintype "passive"))
    )
    (net (code "159") (name "TYPEC1_RX2_P") (class "Default")
      (node (ref "J5") (pin "199") (pinfunction "TYPEC1_RX2P_199") (pintype "passive"))
    )
    (net (code "160") (name "TYPEC1_SBU1") (class "Default")
      (node (ref "J5") (pin "205") (pinfunction "TYPEC1_SBU1_205") (pintype "passive"))
    )
    (net (code "161") (name "TYPEC1_SBU1_DC") (class "Default")
      (node (ref "J5") (pin "211") (pinfunction "TYPEC1_SBU1_DC_211") (pintype "passive"))
    )
    (net (code "162") (name "TYPEC1_SBU2") (class "Default")
      (node (ref "J5") (pin "207") (pinfunction "TYPEC1_SBU2_207") (pintype "passive"))
    )
    (net (code "163") (name "TYPEC1_SBU2_DC") (class "Default")
      (node (ref "J5") (pin "213") (pinfunction "TYPEC1_SBU2_DC_213") (pintype "passive"))
    )
    (net (code "164") (name "TYPEC1_TX1_N") (class "Default")
      (node (ref "J5") (pin "183") (pinfunction "USB3.0/TYPEC1_TX1M_183") (pintype "passive"))
    )
    (net (code "165") (name "TYPEC1_TX1_P") (class "Default")
      (node (ref "J5") (pin "181") (pinfunction "USB3.0/TYPEC1_TX1P_181") (pintype "passive"))
    )
    (net (code "166") (name "TYPEC1_TX2_N") (class "Default")
      (node (ref "J5") (pin "195") (pinfunction "TYPEC1_TX2M_195") (pintype "passive"))
    )
    (net (code "167") (name "TYPEC1_TX2_P") (class "Default")
      (node (ref "J5") (pin "193") (pinfunction "TYPEC1_TX2P_193") (pintype "passive"))
    )
    (net (code "168") (name "TYPEC1_U2VBUSDET") (class "Default")
      (node (ref "J5") (pin "215") (pinfunction "TYPEC1_U2VBUSDET_215") (pintype "passive"))
    )
    (net (code "169") (name "UART2DBG_RX") (class "Default")
      (node (ref "J5") (pin "54") (pinfunction "UART2DBG_RX_54") (pintype "passive"))
    )
    (net (code "170") (name "UART2DBG_TX") (class "Default")
      (node (ref "J5") (pin "52") (pinfunction "UART2DBG_TX_52") (pintype "passive"))
    )
    (net (code "171") (name "VCC1V8_CAM") (class "Default")
      (node (ref "J5") (pin "107") (pinfunction "VCC_1V8_CAM_OUT_107") (pintype "passive"))
    )
    (net (code "172") (name "VCC3V3_SYS") (class "Default")
      (node (ref "J5") (pin "21") (pinfunction "VCC_3V3_OUT_21") (pintype "passive"))
      (node (ref "J5") (pin "23") (pinfunction "VCC_3V3_OUT_23") (pintype "passive"))
      (node (ref "J5") (pin "25") (pinfunction "VCC_3V3_OUT_25") (pintype "passive"))
      (node (ref "J5") (pin "27") (pinfunction "VCC_3V3_OUT_27") (pintype "passive"))
      (node (ref "J5") (pin "33") (pinfunction "VCC_3V3_SLP_OUT_33") (pintype "passive"))
    )
    (net (code "173") (name "VCC5V0_SYS") (class "Default")
      (node (ref "J5") (pin "13") (pinfunction "VCC_5V_OUT_13") (pintype "passive"))
      (node (ref "J5") (pin "15") (pinfunction "VCC_5V_OUT_15") (pintype "passive"))
      (node (ref "J5") (pin "17") (pinfunction "VCC_5V_OUT_17") (pintype "passive"))
      (node (ref "J5") (pin "19") (pinfunction "VCC_5V_OUT_19") (pintype "passive"))
    )
    (net (code "174") (name "VCC_1V8") (class "Default")
      (node (ref "J5") (pin "29") (pinfunction "VCC_1V8_OUT_29") (pintype "passive"))
      (node (ref "J5") (pin "31") (pinfunction "VCC_1V8_OUT_31") (pintype "passive"))
    )
    (net (code "175") (name "VCC_IN_CONN") (class "Default")
      (node (ref "J5") (pin "1") (pinfunction "VCC_DC_IN_1") (pintype "passive"))
      (node (ref "J5") (pin "2") (pinfunction "VCC_DC_IN_2") (pintype "passive"))
      (node (ref "J5") (pin "3") (pinfunction "VCC_DC_IN_3") (pintype "passive"))
      (node (ref "J5") (pin "4") (pinfunction "VCC_DC_IN_4") (pintype "passive"))
      (node (ref "J5") (pin "5") (pinfunction "VCC_DC_IN_5") (pintype "passive"))
      (node (ref "J5") (pin "6") (pinfunction "VCC_DC_IN_6") (pintype "passive"))
      (node (ref "J5") (pin "7") (pinfunction "VCC_DC_IN_7") (pintype "passive"))
      (node (ref "J5") (pin "8") (pinfunction "VCC_DC_IN_8") (pintype "passive"))
    )
    (net (code "176") (name "VDC_ONOFF") (class "Default")
      (node (ref "J5") (pin "16") (pinfunction "VDC_OFF_N_16") (pintype "passive"))
    )
    (net (code "177") (name "unconnected-(J5A-VCC_3V0_SD_OUT-Pad94)") (class "Default")
      (node (ref "J5") (pin "94") (pinfunction "VCC_3V0_SD_OUT_94") (pintype "passive+no_connect"))
    )
  )
)
